# USB2Serial_CP2102_v1_0.net
KiCad netlist of a schematic drawn in EAGLE
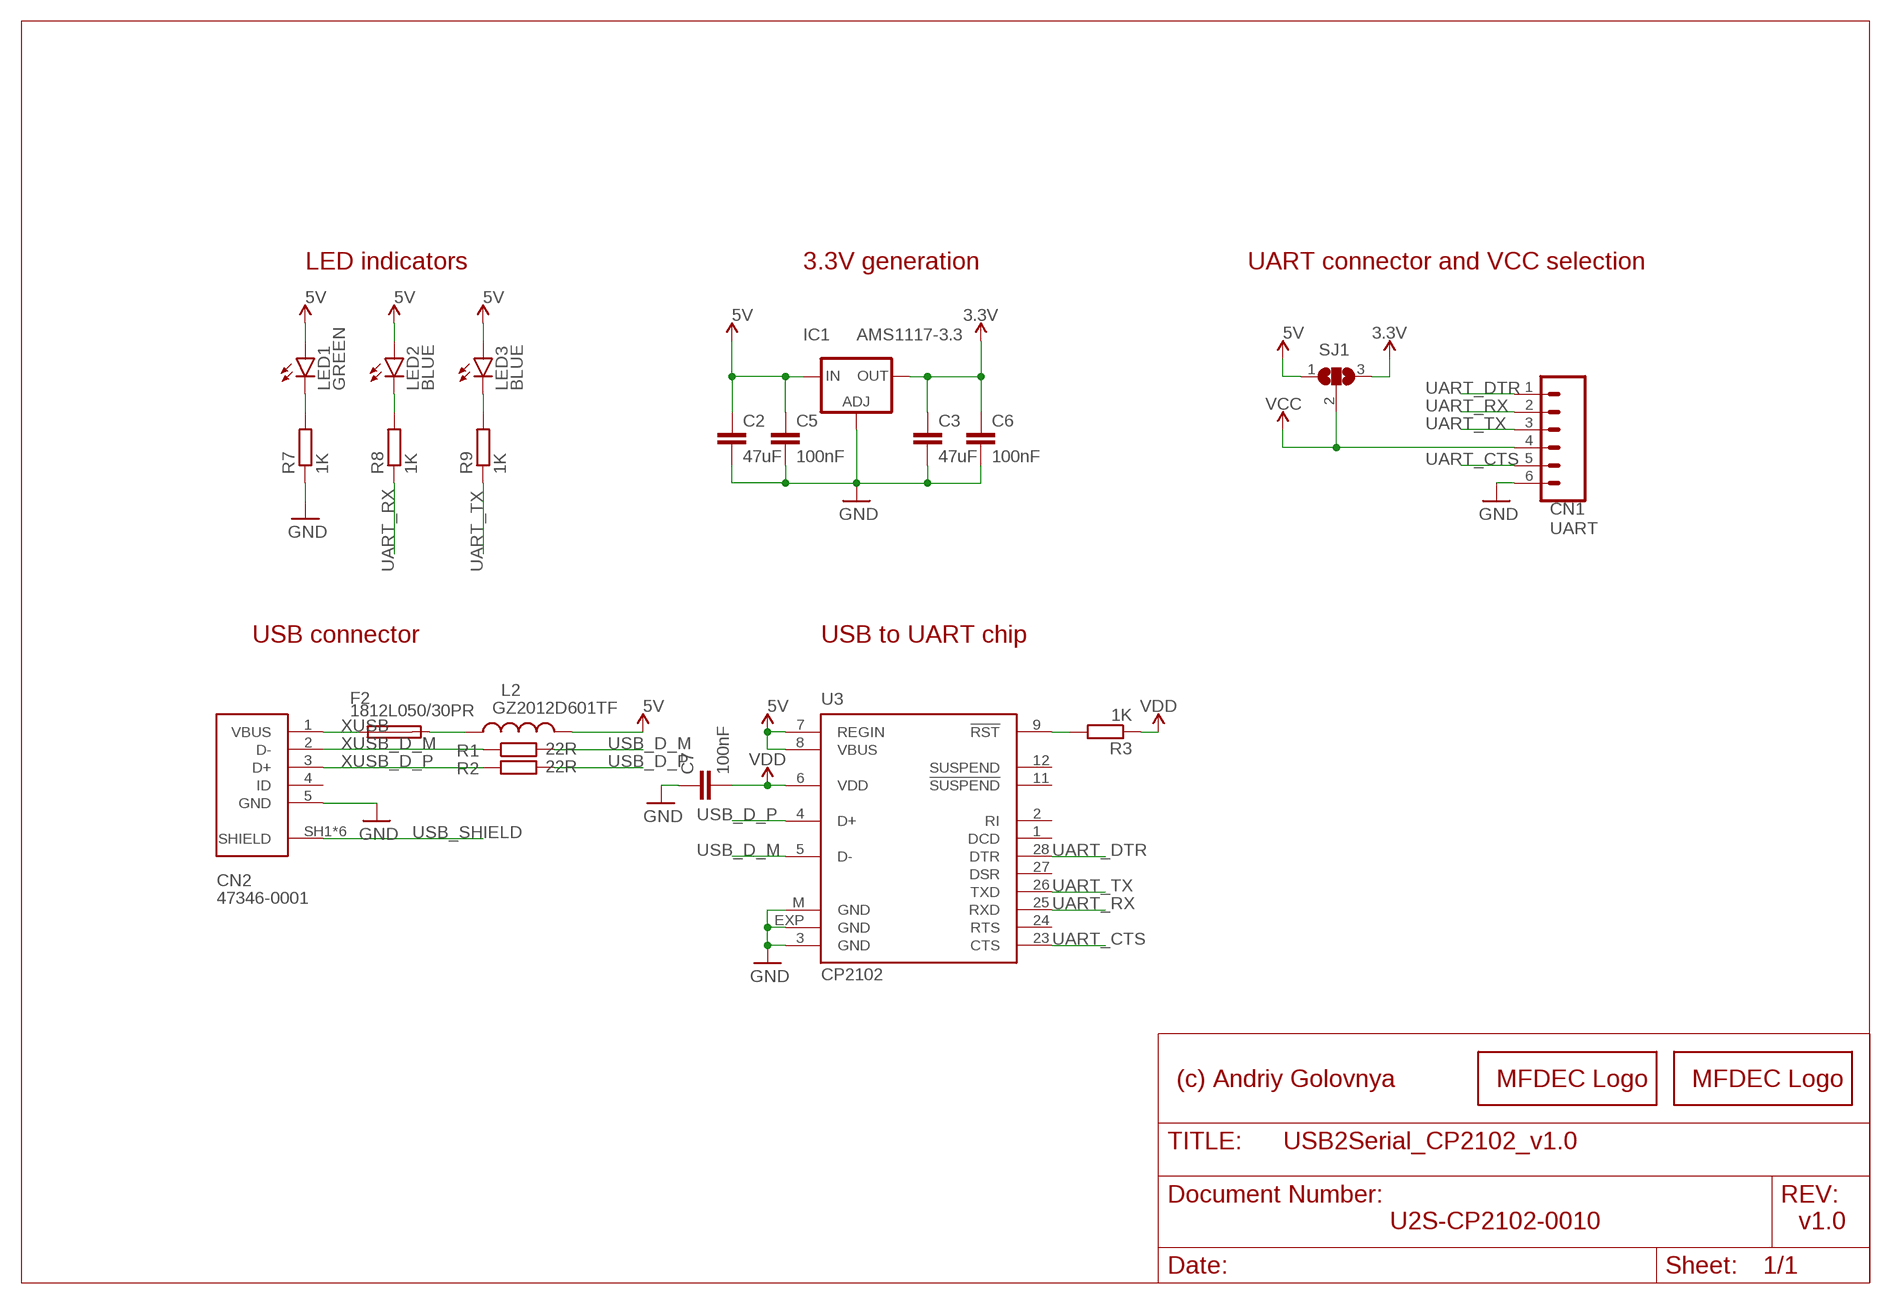
[diagram p0: schematic, sheet 1]

(export (version "E")
  (design (tool "Eeschema 10.0.6"))
  (components
    (comp (ref "C2")
      (value "47uF")
      (footprint "eagle-import:C0805")
      (libsource (lib "eagle-import") (part "C-EUC0805"))
    )
    (comp (ref "C3")
      (value "47uF")
      (footprint "eagle-import:C0805")
      (libsource (lib "eagle-import") (part "C-EUC0805"))
    )
    (comp (ref "C5")
      (value "100nF")
      (footprint "eagle-import:C0402")
      (libsource (lib "eagle-import") (part "C-EUC0402"))
    )
    (comp (ref "C6")
      (value "100nF")
      (footprint "eagle-import:C0402")
      (libsource (lib "eagle-import") (part "C-EUC0402"))
    )
    (comp (ref "C7")
      (value "100nF")
      (footprint "eagle-import:C0402")
      (libsource (lib "eagle-import") (part "C-EUC0402"))
    )
    (comp (ref "CN1")
      (value "UART")
      (footprint "eagle-import:1X06_LOCK")
      (libsource (lib "eagle-import") (part "CONN_06LOCK"))
    )
    (comp (ref "CN2")
      (value "47346-0001")
      (footprint "eagle-import:MOLEX_47346-0001")
      (fields (field (name "MANUFACTURER") "Molex"))
      (libsource (lib "eagle-import") (part "47346-0001"))
    )
    (comp (ref "F2")
      (value "1812L050/30PR")
      (footprint "eagle-import:MF-SMDF050")
      (libsource (lib "eagle-import") (part "MF-SMDF050"))
    )
    (comp (ref "IC1")
      (value "AMS1117-3.3")
      (footprint "eagle-import:SOT223")
      (libsource (lib "eagle-import") (part "LD117A?S33TR"))
    )
    (comp (ref "L2")
      (value "GZ2012D601TF")
      (footprint "eagle-import:WE-CBA_0805(W=4)")
      (libsource (lib "eagle-import") (part "WE-CBA_0805_HC_782853102"))
    )
    (comp (ref "LED1")
      (value "GREEN")
      (footprint "eagle-import:SML0603")
      (libsource (lib "eagle-import") (part "LEDSML0603"))
    )
    (comp (ref "LED2")
      (value "BLUE")
      (footprint "eagle-import:SML0603")
      (libsource (lib "eagle-import") (part "LEDSML0603"))
    )
    (comp (ref "LED3")
      (value "BLUE")
      (footprint "eagle-import:SML0603")
      (libsource (lib "eagle-import") (part "LEDSML0603"))
    )
    (comp (ref "LOGO1")
      (value "MFDECLOGO_L_20MM")
      (footprint "eagle-import:MFDEC_L_20MM")
      (libsource (lib "eagle-import") (part "MFDECLOGO_L_20MM"))
    )
    (comp (ref "LOGO2")
      (value "MFDECLOGO_SQ_10MM")
      (footprint "eagle-import:MFDEC_SQ_10MM")
      (libsource (lib "eagle-import") (part "MFDECLOGO_SQ_10MM"))
    )
    (comp (ref "R1")
      (value "22R")
      (footprint "eagle-import:R0402")
      (libsource (lib "eagle-import") (part "R-EU_R0402"))
    )
    (comp (ref "R2")
      (value "22R")
      (footprint "eagle-import:R0402")
      (libsource (lib "eagle-import") (part "R-EU_R0402"))
    )
    (comp (ref "R3")
      (value "1K")
      (footprint "eagle-import:R0402")
      (libsource (lib "eagle-import") (part "R-EU_R0402"))
    )
    (comp (ref "R7")
      (value "1K")
      (footprint "eagle-import:R0402")
      (libsource (lib "eagle-import") (part "R-EU_R0402"))
    )
    (comp (ref "R8")
      (value "1K")
      (footprint "eagle-import:R0402")
      (libsource (lib "eagle-import") (part "R-EU_R0402"))
    )
    (comp (ref "R9")
      (value "1K")
      (footprint "eagle-import:R0402")
      (libsource (lib "eagle-import") (part "R-EU_R0402"))
    )
    (comp (ref "SJ1")
      (value "SJ2FI")
      (footprint "eagle-import:SJ_2FI")
      (libsource (lib "eagle-import") (part "SJ2FI"))
    )
    (comp (ref "U3")
      (value "CP2102")
      (footprint "eagle-import:MLP28")
      (fields (field (name "MF") "FARNELL") (field (name "MPN") "CP2102-GM"))
      (libsource (lib "eagle-import") (part "CP2102"))
    )
  )
  (nets
    (net (code "1") (name "/UART_CTS") (class "Default")
      (node (ref "CN1") (pin "5") (pinfunction "5_5") (pintype "passive"))
      (node (ref "U3") (pin "23") (pinfunction "CTS_23") (pintype "input"))
    )
    (net (code "2") (name "/UART_DTR") (class "Default")
      (node (ref "CN1") (pin "1") (pinfunction "1_1") (pintype "passive"))
      (node (ref "U3") (pin "28") (pinfunction "DTR_28") (pintype "output"))
    )
    (net (code "3") (name "/UART_RX") (class "Default")
      (node (ref "CN1") (pin "2") (pinfunction "2_2") (pintype "passive"))
      (node (ref "R8") (pin "1") (pinfunction "1_1") (pintype "passive"))
      (node (ref "U3") (pin "25") (pinfunction "RXD_25") (pintype "input"))
    )
    (net (code "4") (name "/UART_TX") (class "Default")
      (node (ref "CN1") (pin "3") (pinfunction "3_3") (pintype "passive"))
      (node (ref "R9") (pin "1") (pinfunction "1_1") (pintype "passive"))
      (node (ref "U3") (pin "26") (pinfunction "TXD_26") (pintype "output"))
    )
    (net (code "5") (name "/USB_D_M") (class "Default")
      (node (ref "R1") (pin "2") (pinfunction "2_2") (pintype "passive"))
      (node (ref "U3") (pin "5") (pinfunction "D-_5") (pintype "bidirectional"))
    )
    (net (code "6") (name "/USB_D_P") (class "Default")
      (node (ref "R2") (pin "2") (pinfunction "2_2") (pintype "passive"))
      (node (ref "U3") (pin "4") (pinfunction "D+_4") (pintype "bidirectional"))
    )
    (net (code "7") (name "/USB_SHIELD") (class "Default")
      (node (ref "CN2") (pin "SH1") (pinfunction "SHIELD_SH1") (pintype "passive"))
      (node (ref "CN2") (pin "SH2") (pinfunction "SHIELD_SH2") (pintype "passive"))
      (node (ref "CN2") (pin "SH3") (pinfunction "SHIELD_SH3") (pintype "passive"))
      (node (ref "CN2") (pin "SH4") (pinfunction "SHIELD_SH4") (pintype "passive"))
      (node (ref "CN2") (pin "SH5") (pinfunction "SHIELD_SH5") (pintype "passive"))
      (node (ref "CN2") (pin "SH6") (pinfunction "SHIELD_SH6") (pintype "passive"))
    )
    (net (code "8") (name "/XUSB") (class "Default")
      (node (ref "CN2") (pin "1") (pinfunction "VBUS_1") (pintype "power_in"))
      (node (ref "F2") (pin "1") (pinfunction "1_1") (pintype "passive"))
    )
    (net (code "9") (name "/XUSB_D_M") (class "Default")
      (node (ref "CN2") (pin "2") (pinfunction "D-_2") (pintype "bidirectional"))
      (node (ref "R1") (pin "1") (pinfunction "1_1") (pintype "passive"))
    )
    (net (code "10") (name "/XUSB_D_P") (class "Default")
      (node (ref "CN2") (pin "3") (pinfunction "D+_3") (pintype "bidirectional"))
      (node (ref "R2") (pin "1") (pinfunction "1_1") (pintype "passive"))
    )
    (net (code "11") (name "3.3V") (class "Default")
      (node (ref "C3") (pin "1") (pinfunction "1_1") (pintype "passive"))
      (node (ref "C6") (pin "1") (pinfunction "1_1") (pintype "passive"))
      (node (ref "IC1") (pin "4") (pinfunction "OUT_4") (pintype "passive"))
      (node (ref "SJ1") (pin "3") (pinfunction "3_3") (pintype "passive"))
    )
    (net (code "12") (name "5V") (class "Default")
      (node (ref "C2") (pin "1") (pinfunction "1_1") (pintype "passive"))
      (node (ref "C5") (pin "1") (pinfunction "1_1") (pintype "passive"))
      (node (ref "IC1") (pin "3") (pinfunction "IN_3") (pintype "input"))
      (node (ref "L2") (pin "2") (pinfunction "2_2") (pintype "passive"))
      (node (ref "LED1") (pin "A") (pinfunction "A_A") (pintype "passive"))
      (node (ref "LED2") (pin "A") (pinfunction "A_A") (pintype "passive"))
      (node (ref "LED3") (pin "A") (pinfunction "A_A") (pintype "passive"))
      (node (ref "SJ1") (pin "1") (pinfunction "1_1") (pintype "passive"))
      (node (ref "U3") (pin "7") (pinfunction "REGIN_7") (pintype "passive"))
      (node (ref "U3") (pin "8") (pinfunction "VBUS_8") (pintype "input"))
    )
    (net (code "13") (name "GND") (class "Default")
      (node (ref "C2") (pin "2") (pinfunction "2_2") (pintype "passive"))
      (node (ref "C3") (pin "2") (pinfunction "2_2") (pintype "passive"))
      (node (ref "C5") (pin "2") (pinfunction "2_2") (pintype "passive"))
      (node (ref "C6") (pin "2") (pinfunction "2_2") (pintype "passive"))
      (node (ref "C7") (pin "1") (pinfunction "1_1") (pintype "passive"))
      (node (ref "CN1") (pin "6") (pinfunction "6_6") (pintype "passive"))
      (node (ref "CN2") (pin "5") (pinfunction "GND_5") (pintype "power_in"))
      (node (ref "IC1") (pin "1") (pinfunction "ADJ_1") (pintype "input"))
      (node (ref "R7") (pin "1") (pinfunction "1_1") (pintype "passive"))
      (node (ref "U3") (pin "3") (pinfunction "GND_3") (pintype "power_in"))
      (node (ref "U3") (pin "EXP") (pinfunction "GND_EXP") (pintype "power_in"))
      (node (ref "U3") (pin "M") (pinfunction "GND_M") (pintype "power_in"))
    )
    (net (code "14") (name "Net-(F2-Pad2)") (class "Default")
      (node (ref "F2") (pin "2") (pinfunction "2_2") (pintype "passive"))
      (node (ref "L2") (pin "1") (pinfunction "1_1") (pintype "passive"))
    )
    (net (code "15") (name "Net-(LED1-PadC)") (class "Default")
      (node (ref "LED1") (pin "C") (pinfunction "C_C") (pintype "passive"))
      (node (ref "R7") (pin "2") (pinfunction "2_2") (pintype "passive"))
    )
    (net (code "16") (name "Net-(LED2-PadC)") (class "Default")
      (node (ref "LED2") (pin "C") (pinfunction "C_C") (pintype "passive"))
      (node (ref "R8") (pin "2") (pinfunction "2_2") (pintype "passive"))
    )
    (net (code "17") (name "Net-(LED3-PadC)") (class "Default")
      (node (ref "LED3") (pin "C") (pinfunction "C_C") (pintype "passive"))
      (node (ref "R9") (pin "2") (pinfunction "2_2") (pintype "passive"))
    )
    (net (code "18") (name "Net-(U3-~{RST})") (class "Default")
      (node (ref "R3") (pin "2") (pinfunction "2_2") (pintype "passive"))
      (node (ref "U3") (pin "9") (pinfunction "~{RST}_9") (pintype "bidirectional"))
    )
    (net (code "19") (name "VCC") (class "Default")
      (node (ref "CN1") (pin "4") (pinfunction "4_4") (pintype "passive"))
      (node (ref "SJ1") (pin "2") (pinfunction "2_2") (pintype "passive"))
    )
    (net (code "20") (name "VDD") (class "Default")
      (node (ref "C7") (pin "2") (pinfunction "2_2") (pintype "passive"))
      (node (ref "R3") (pin "1") (pinfunction "1_1") (pintype "passive"))
      (node (ref "U3") (pin "6") (pinfunction "VDD_6") (pintype "power_in"))
    )
    (net (code "21") (name "unconnected-(CN2-ID-Pad4)") (class "Default")
      (node (ref "CN2") (pin "4") (pinfunction "ID_4") (pintype "passive"))
    )
    (net (code "22") (name "unconnected-(U3-DCD-Pad1)") (class "Default")
      (node (ref "U3") (pin "1") (pinfunction "DCD_1") (pintype "input"))
    )
    (net (code "23") (name "unconnected-(U3-DSR-Pad27)") (class "Default")
      (node (ref "U3") (pin "27") (pinfunction "DSR_27") (pintype "input"))
    )
    (net (code "24") (name "unconnected-(U3-RI-Pad2)") (class "Default")
      (node (ref "U3") (pin "2") (pinfunction "RI_2") (pintype "input"))
    )
    (net (code "25") (name "unconnected-(U3-RTS-Pad24)") (class "Default")
      (node (ref "U3") (pin "24") (pinfunction "RTS_24") (pintype "output"))
    )
    (net (code "26") (name "unconnected-(U3-SUSPEND-Pad12)") (class "Default")
      (node (ref "U3") (pin "12") (pinfunction "SUSPEND_12") (pintype "output"))
    )
    (net (code "27") (name "unconnected-(U3-~{SUSPEND}-Pad11)") (class "Default")
      (node (ref "U3") (pin "11") (pinfunction "~{SUSPEND}_11") (pintype "output"))
    )
  )
)
